# four.net
KiCad netlist of a schematic drawn in EAGLE
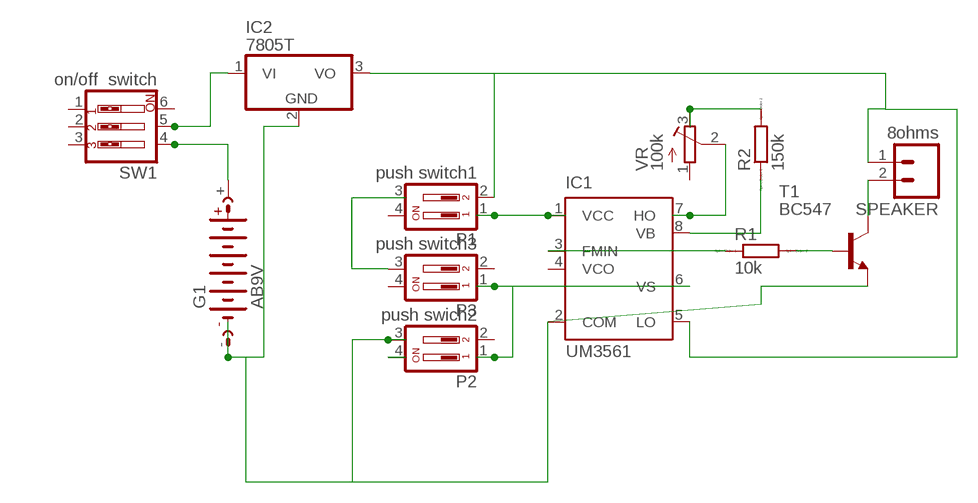
[diagram p0: schematic, sheet 1]

(export (version "E")
  (design (tool "Eeschema 10.0.6"))
  (components
    (comp (ref "G1")
      (value "AB9V")
      (footprint "eagle-import:AB9V")
      (libsource (lib "eagle-import") (part "AB9V"))
    )
    (comp (ref "IC1")
      (value "UM3561")
      (footprint "eagle-import:DIL08")
      (fields (field (name "MF") "INTERNATIONAL RECTIFIER(IR)") (field (name "MPN") "IR2520DPBF"))
      (libsource (lib "eagle-import") (part "IR2520D"))
    )
    (comp (ref "IC2")
      (value "7805T")
      (footprint "eagle-import:TO220H")
      (libsource (lib "eagle-import") (part "78T05"))
    )
    (comp (ref "P1")
      (value "push switch1")
      (footprint "eagle-import:DS-02")
      (libsource (lib "eagle-import") (part "DS02"))
    )
    (comp (ref "P2")
      (value "push swich2")
      (footprint "eagle-import:DS-02")
      (libsource (lib "eagle-import") (part "DS02"))
    )
    (comp (ref "P3")
      (value "push switch3")
      (footprint "eagle-import:DS-02")
      (libsource (lib "eagle-import") (part "DS02"))
    )
    (comp (ref "R1")
      (value "10k")
      (footprint "eagle-import:0204_7")
      (libsource (lib "eagle-import") (part "R0204/7"))
    )
    (comp (ref "R2")
      (value "150k")
      (footprint "eagle-import:0204_7")
      (libsource (lib "eagle-import") (part "R0204/7"))
    )
    (comp (ref "SPEAKER")
      (value "8ohms")
      (footprint "eagle-import:02P")
      (libsource (lib "eagle-import") (part "M02"))
    )
    (comp (ref "SW1")
      (value "on/off switch")
      (footprint "eagle-import:EDG-03")
      (libsource (lib "eagle-import") (part "SW_DIP-3"))
    )
    (comp (ref "T1")
      (value "BC547")
      (footprint "eagle-import:TO92")
      (libsource (lib "eagle-import") (part "BC547"))
    )
    (comp (ref "VR")
      (value "100k")
      (footprint "eagle-import:RTRIM64P")
      (libsource (lib "eagle-import") (part "R-TRIMM64P"))
    )
  )
  (nets
    (net (code "1") (name "Net-(G1-Pad+)") (class "Default")
      (node (ref "G1") (pin "+") (pinfunction "+_+") (pintype "passive"))
      (node (ref "SW1") (pin "4") (pinfunction "4_4") (pintype "passive"))
    )
    (net (code "2") (name "Net-(IC1-COM)") (class "Default")
      (node (ref "G1") (pin "-") (pinfunction "-_-") (pintype "passive"))
      (node (ref "IC1") (pin "2") (pinfunction "COM_2") (pintype "power_in"))
      (node (ref "IC2") (pin "2") (pinfunction "GND_2") (pintype "passive"))
      (node (ref "P2") (pin "3") (pinfunction "3_3") (pintype "passive"))
      (node (ref "T1") (pin "1") (pinfunction "E_1") (pintype "passive"))
    )
    (net (code "3") (name "Net-(IC1-FMIN)") (class "Default")
      (node (ref "IC1") (pin "3") (pinfunction "FMIN_3") (pintype "input"))
      (node (ref "R1") (pin "1") (pinfunction "1_1") (pintype "passive"))
    )
    (net (code "4") (name "Net-(IC1-HO)") (class "Default")
      (node (ref "IC1") (pin "7") (pinfunction "HO_7") (pintype "output"))
      (node (ref "VR") (pin "2") (pinfunction "S_2") (pintype "passive"))
    )
    (net (code "5") (name "Net-(IC1-LO)") (class "Default")
      (node (ref "IC1") (pin "5") (pinfunction "LO_5") (pintype "output"))
      (node (ref "IC2") (pin "3") (pinfunction "VO_3") (pintype "passive"))
      (node (ref "P1") (pin "2") (pinfunction "2_2") (pintype "passive"))
      (node (ref "SPEAKER") (pin "1") (pinfunction "1_1") (pintype "passive"))
    )
    (net (code "6") (name "Net-(IC1-VB)") (class "Default")
      (node (ref "IC1") (pin "8") (pinfunction "VB_8") (pintype "passive"))
      (node (ref "R2") (pin "1") (pinfunction "1_1") (pintype "passive"))
    )
    (net (code "7") (name "Net-(IC1-VCC)") (class "Default")
      (node (ref "IC1") (pin "1") (pinfunction "VCC_1") (pintype "power_in"))
      (node (ref "P1") (pin "1") (pinfunction "1_1") (pintype "passive"))
    )
    (net (code "8") (name "Net-(IC1-VS)") (class "Default")
      (node (ref "IC1") (pin "6") (pinfunction "VS_6") (pintype "input"))
      (node (ref "P2") (pin "1") (pinfunction "1_1") (pintype "passive"))
      (node (ref "P3") (pin "1") (pinfunction "1_1") (pintype "passive"))
    )
    (net (code "9") (name "Net-(IC2-VI)") (class "Default")
      (node (ref "IC2") (pin "1") (pinfunction "VI_1") (pintype "input"))
      (node (ref "SW1") (pin "5") (pinfunction "5_5") (pintype "passive"))
    )
    (net (code "10") (name "Net-(P1-Pad3)") (class "Default")
      (node (ref "P1") (pin "3") (pinfunction "3_3") (pintype "passive"))
      (node (ref "P3") (pin "3") (pinfunction "3_3") (pintype "passive"))
    )
    (net (code "11") (name "Net-(T1-B)") (class "Default")
      (node (ref "R1") (pin "2") (pinfunction "2_2") (pintype "passive"))
      (node (ref "T1") (pin "2") (pinfunction "B_2") (pintype "passive"))
    )
    (net (code "12") (name "Net-(T1-C)") (class "Default")
      (node (ref "SPEAKER") (pin "2") (pinfunction "2_2") (pintype "passive"))
      (node (ref "T1") (pin "3") (pinfunction "C_3") (pintype "passive"))
    )
    (net (code "13") (name "Net-(VR-A)") (class "Default")
      (node (ref "R2") (pin "2") (pinfunction "2_2") (pintype "passive"))
      (node (ref "VR") (pin "3") (pinfunction "A_3") (pintype "passive"))
    )
    (net (code "14") (name "unconnected-(IC1-VCO-Pad4)") (class "Default")
      (node (ref "IC1") (pin "4") (pinfunction "VCO_4") (pintype "input"))
    )
    (net (code "15") (name "unconnected-(P1-Pad4)") (class "Default")
      (node (ref "P1") (pin "4") (pinfunction "4_4") (pintype "passive"))
    )
    (net (code "16") (name "unconnected-(P2-Pad2)") (class "Default")
      (node (ref "P2") (pin "2") (pinfunction "2_2") (pintype "passive"))
    )
    (net (code "17") (name "unconnected-(P2-Pad4)") (class "Default")
      (node (ref "P2") (pin "4") (pinfunction "4_4") (pintype "passive"))
    )
    (net (code "18") (name "unconnected-(P3-Pad2)") (class "Default")
      (node (ref "P3") (pin "2") (pinfunction "2_2") (pintype "passive"))
    )
    (net (code "19") (name "unconnected-(P3-Pad4)") (class "Default")
      (node (ref "P3") (pin "4") (pinfunction "4_4") (pintype "passive"))
    )
    (net (code "20") (name "unconnected-(SW1-Pad1)") (class "Default")
      (node (ref "SW1") (pin "1") (pinfunction "1_1") (pintype "passive"))
    )
    (net (code "21") (name "unconnected-(SW1-Pad2)") (class "Default")
      (node (ref "SW1") (pin "2") (pinfunction "2_2") (pintype "passive"))
    )
    (net (code "22") (name "unconnected-(SW1-Pad3)") (class "Default")
      (node (ref "SW1") (pin "3") (pinfunction "3_3") (pintype "passive"))
    )
    (net (code "23") (name "unconnected-(SW1-Pad6)") (class "Default")
      (node (ref "SW1") (pin "6") (pinfunction "6_6") (pintype "passive"))
    )
    (net (code "24") (name "unconnected-(VR-E-Pad1)") (class "Default")
      (node (ref "VR") (pin "1") (pinfunction "E_1") (pintype "passive"))
    )
  )
)
